# PCB-CMB-1.net
KiCad netlist of a schematic drawn in EAGLE
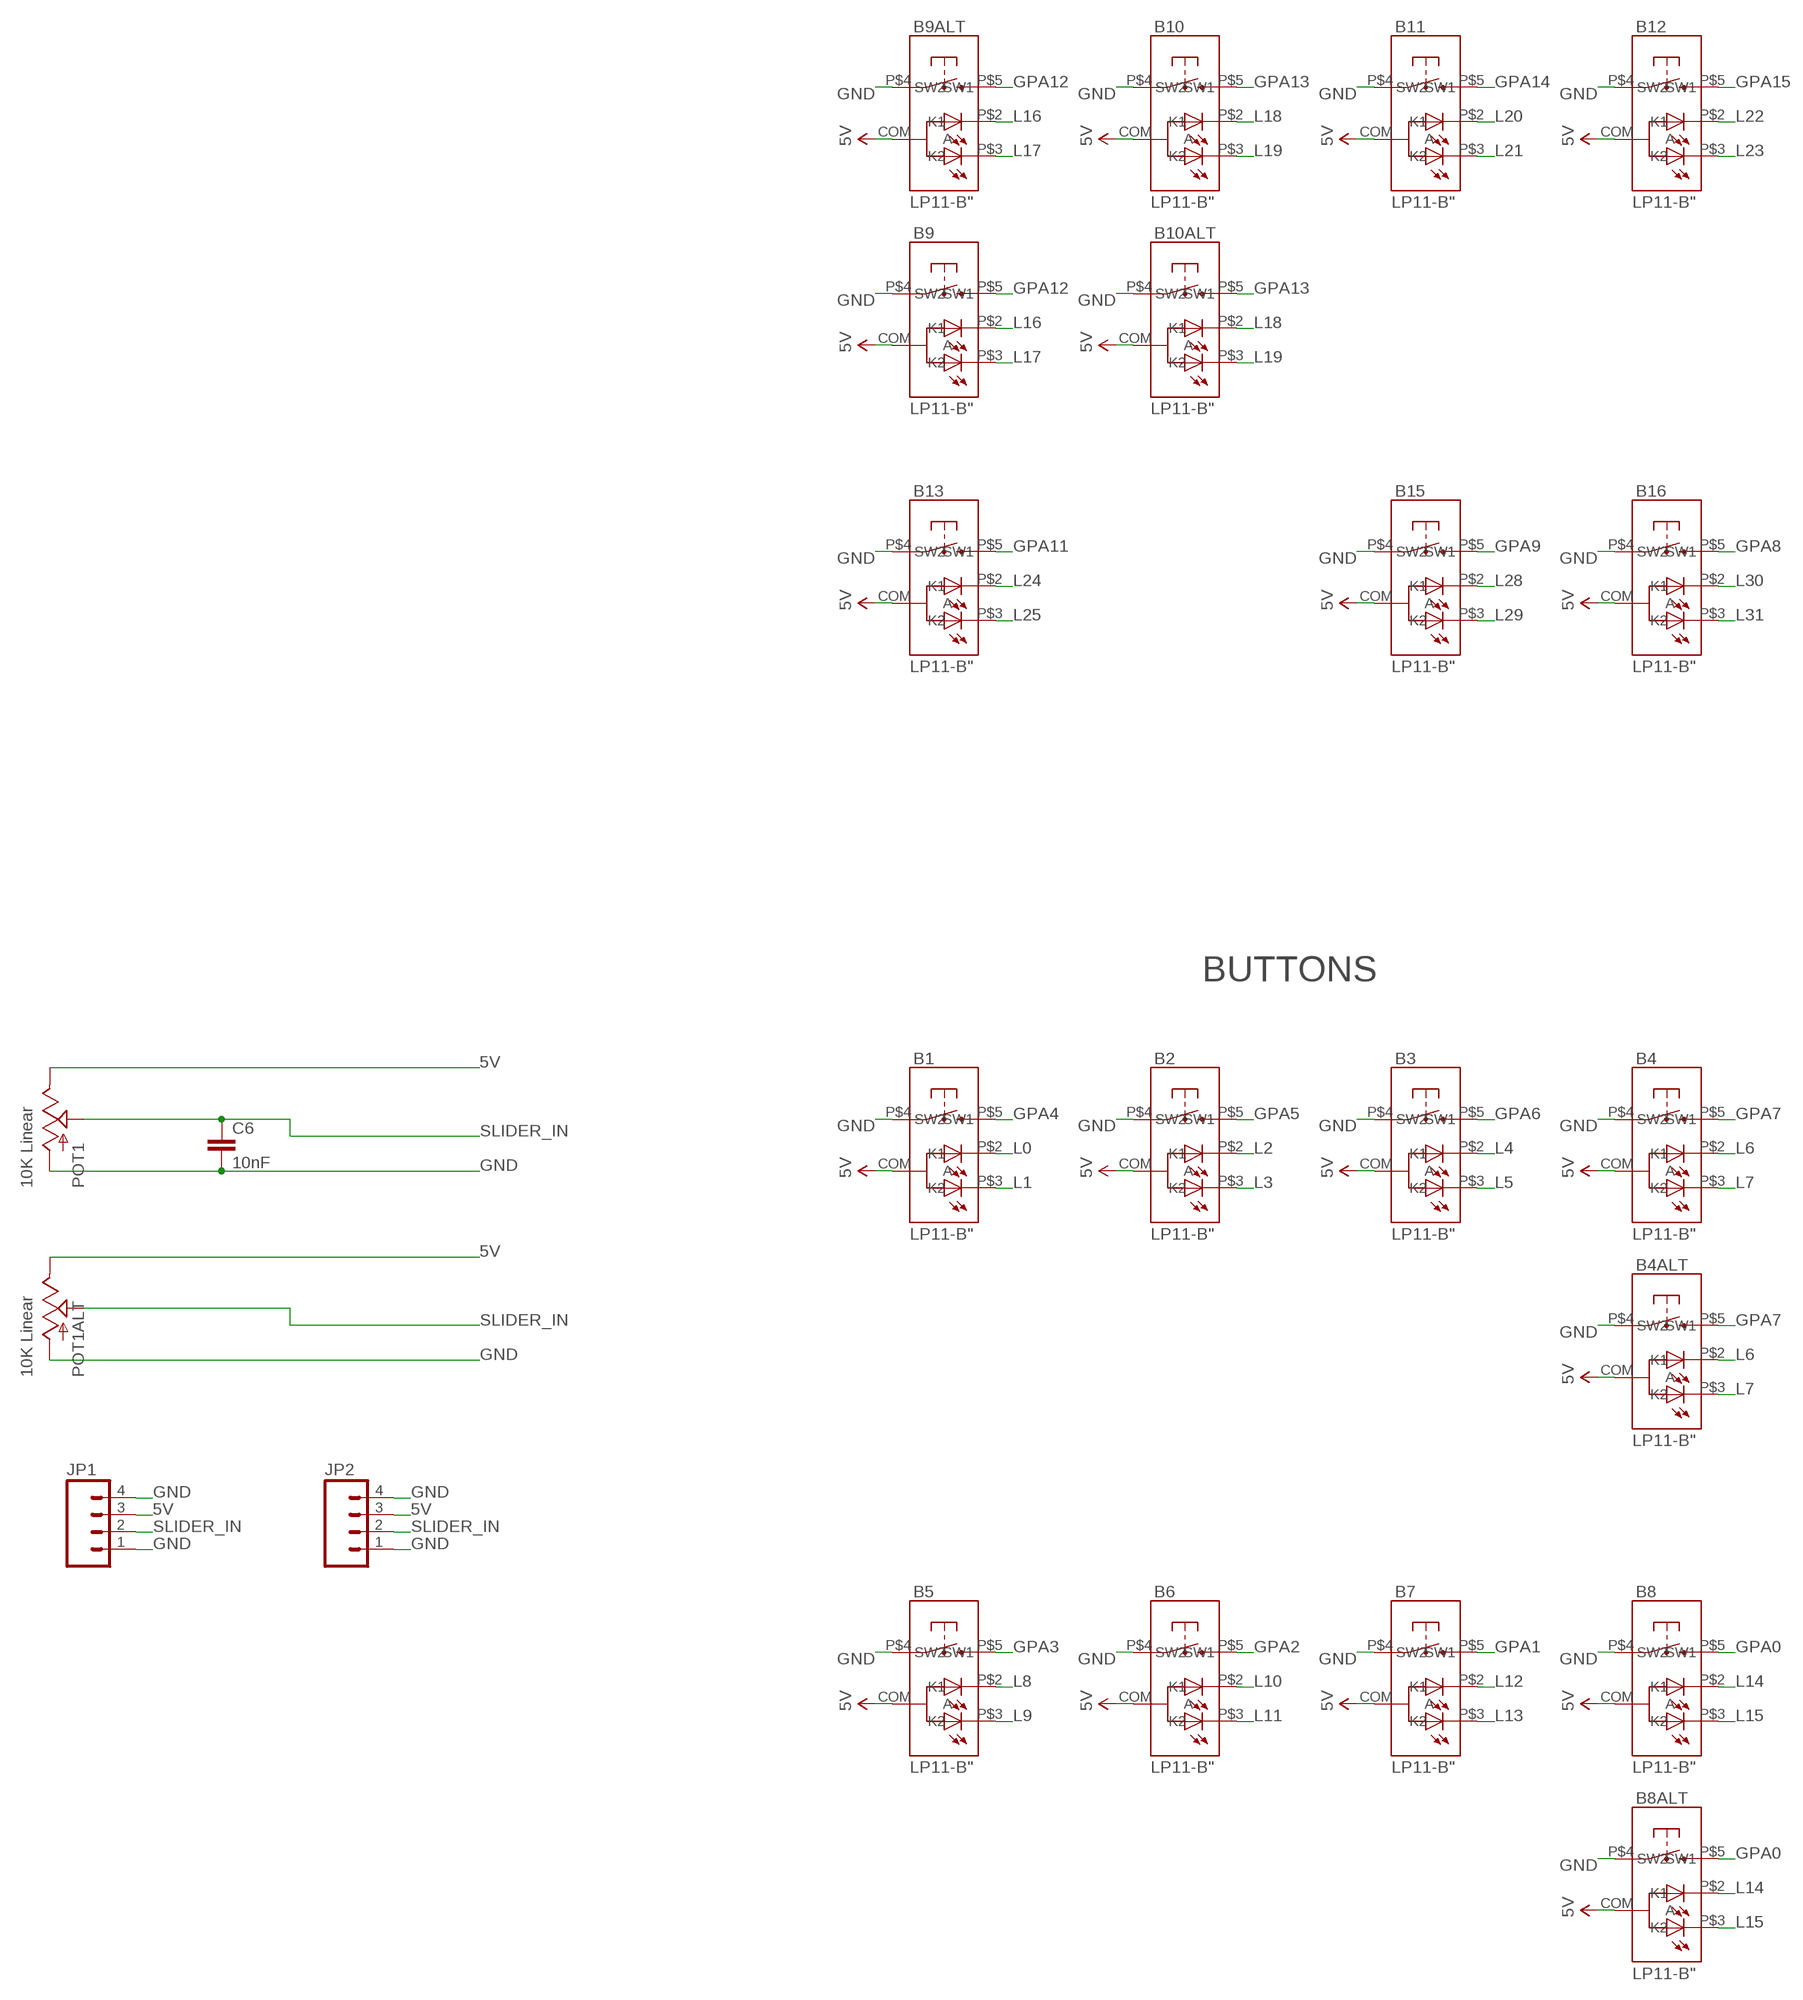
[diagram p0: schematic, sheet 1, part 1 of 2]
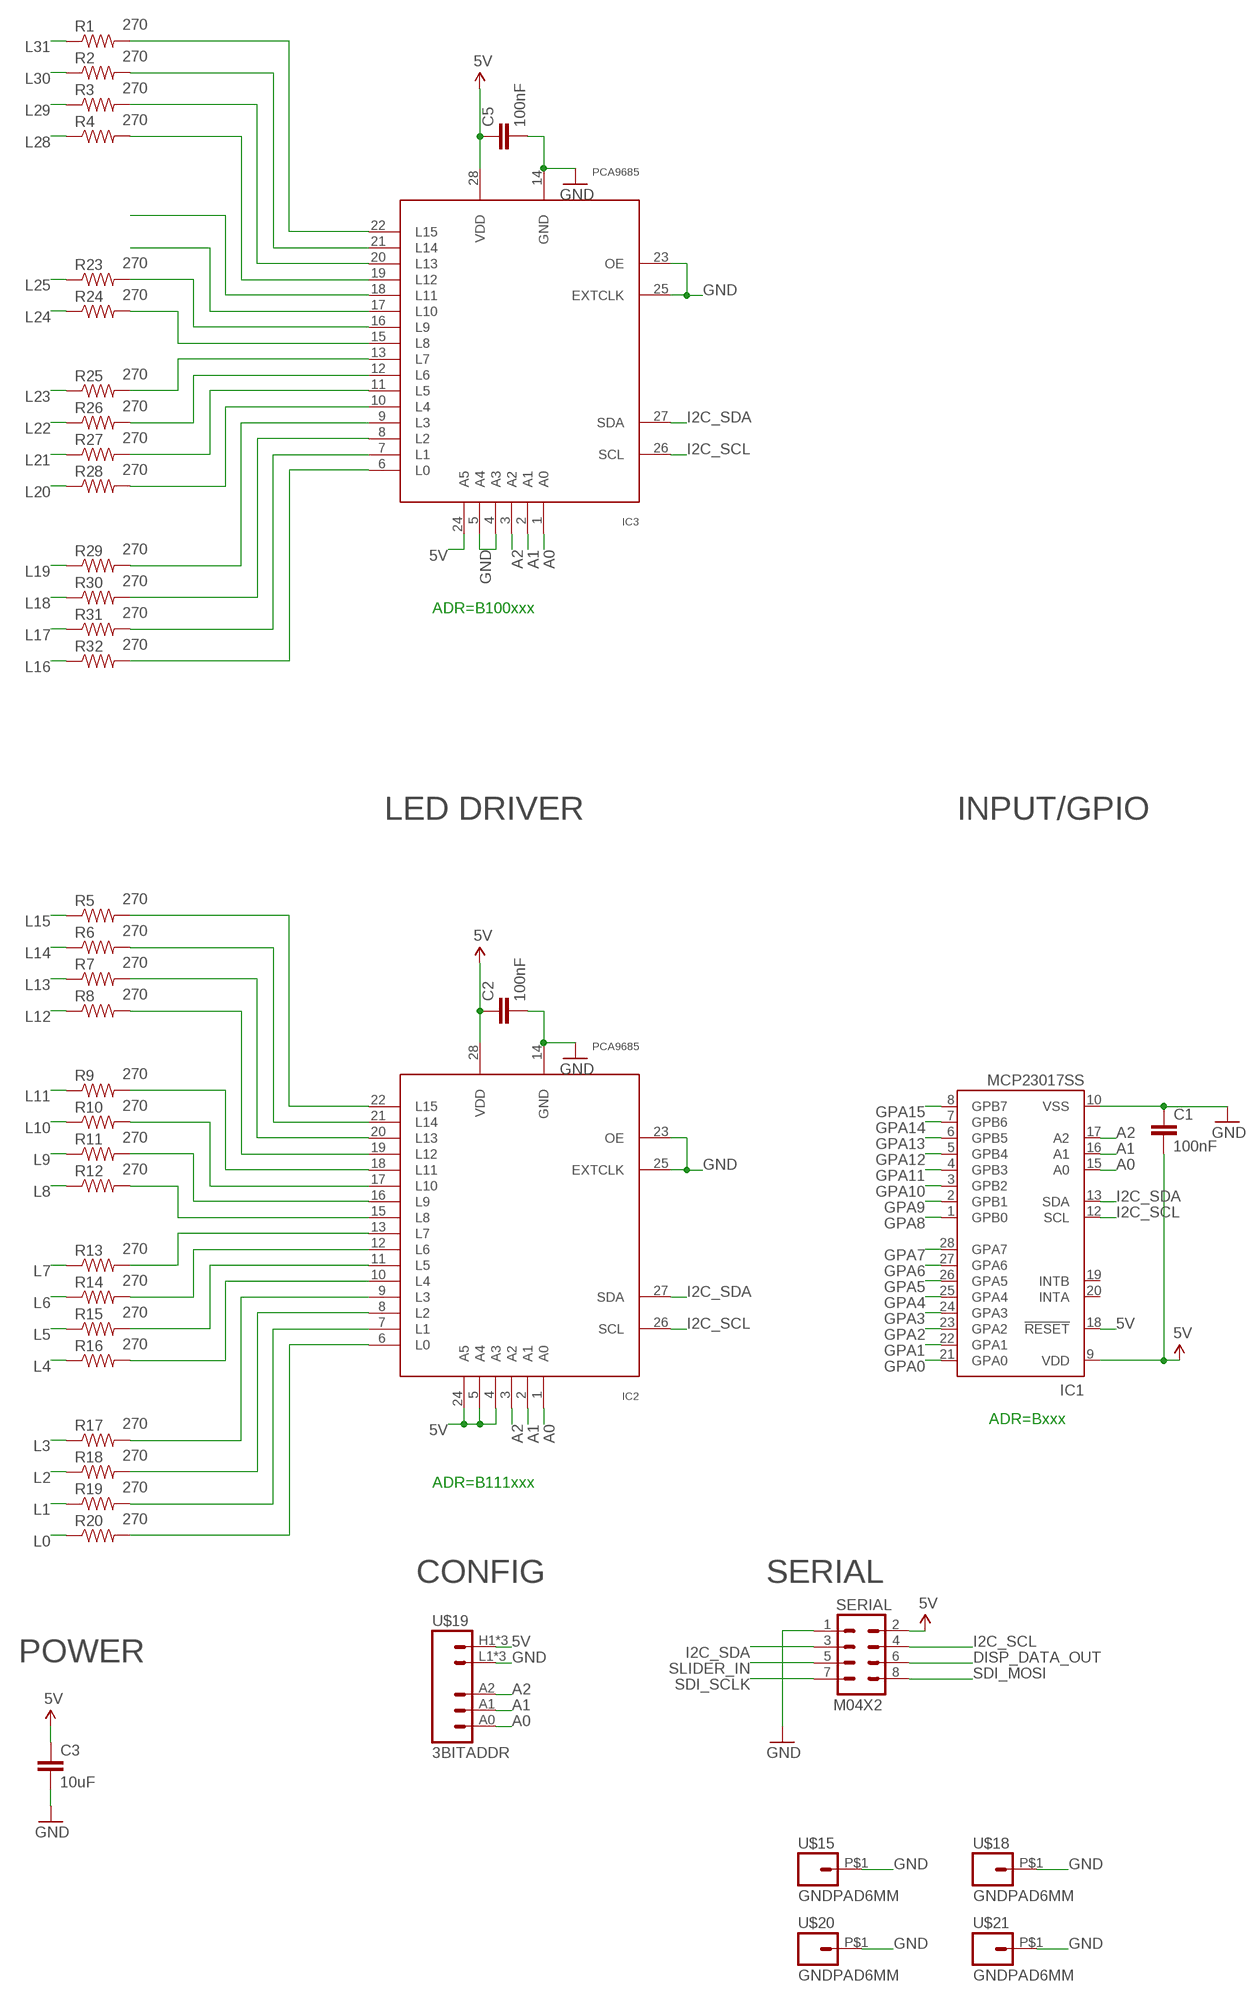
[diagram p1: schematic, sheet 1, part 2 of 2]

(export (version "E")
  (design (tool "Eeschema 10.0.6"))
  (components
    (comp (ref "B1")
      (value "LP11-B\"")
      (footprint "eagle-import:LP11")
      (libsource (lib "eagle-import") (part "LP11-B{dblquote}"))
    )
    (comp (ref "B2")
      (value "LP11-B\"")
      (footprint "eagle-import:LP11")
      (libsource (lib "eagle-import") (part "LP11-B{dblquote}"))
    )
    (comp (ref "B3")
      (value "LP11-B\"")
      (footprint "eagle-import:LP11")
      (libsource (lib "eagle-import") (part "LP11-B{dblquote}"))
    )
    (comp (ref "B4")
      (value "LP11-B\"")
      (footprint "eagle-import:LP11")
      (libsource (lib "eagle-import") (part "LP11-B{dblquote}"))
    )
    (comp (ref "B4ALT")
      (value "LP11-B\"")
      (footprint "eagle-import:LP11")
      (libsource (lib "eagle-import") (part "LP11-B{dblquote}"))
    )
    (comp (ref "B5")
      (value "LP11-B\"")
      (footprint "eagle-import:LP11")
      (libsource (lib "eagle-import") (part "LP11-B{dblquote}"))
    )
    (comp (ref "B6")
      (value "LP11-B\"")
      (footprint "eagle-import:LP11")
      (libsource (lib "eagle-import") (part "LP11-B{dblquote}"))
    )
    (comp (ref "B7")
      (value "LP11-B\"")
      (footprint "eagle-import:LP11")
      (libsource (lib "eagle-import") (part "LP11-B{dblquote}"))
    )
    (comp (ref "B8")
      (value "LP11-B\"")
      (footprint "eagle-import:LP11")
      (libsource (lib "eagle-import") (part "LP11-B{dblquote}"))
    )
    (comp (ref "B8ALT")
      (value "LP11-B\"")
      (footprint "eagle-import:LP11")
      (libsource (lib "eagle-import") (part "LP11-B{dblquote}"))
    )
    (comp (ref "B9")
      (value "LP11-B\"")
      (footprint "eagle-import:LP11")
      (libsource (lib "eagle-import") (part "LP11-B{dblquote}"))
    )
    (comp (ref "B9ALT")
      (value "LP11-B\"")
      (footprint "eagle-import:LP11")
      (libsource (lib "eagle-import") (part "LP11-B{dblquote}"))
    )
    (comp (ref "B10")
      (value "LP11-B\"")
      (footprint "eagle-import:LP11")
      (libsource (lib "eagle-import") (part "LP11-B{dblquote}"))
    )
    (comp (ref "B10ALT")
      (value "LP11-B\"")
      (footprint "eagle-import:LP11")
      (libsource (lib "eagle-import") (part "LP11-B{dblquote}"))
    )
    (comp (ref "B11")
      (value "LP11-B\"")
      (footprint "eagle-import:LP11")
      (libsource (lib "eagle-import") (part "LP11-B{dblquote}"))
    )
    (comp (ref "B12")
      (value "LP11-B\"")
      (footprint "eagle-import:LP11")
      (libsource (lib "eagle-import") (part "LP11-B{dblquote}"))
    )
    (comp (ref "B13")
      (value "LP11-B\"")
      (footprint "eagle-import:LP11")
      (libsource (lib "eagle-import") (part "LP11-B{dblquote}"))
    )
    (comp (ref "B15")
      (value "LP11-B\"")
      (footprint "eagle-import:LP11")
      (libsource (lib "eagle-import") (part "LP11-B{dblquote}"))
    )
    (comp (ref "B16")
      (value "LP11-B\"")
      (footprint "eagle-import:LP11")
      (libsource (lib "eagle-import") (part "LP11-B{dblquote}"))
    )
    (comp (ref "C1")
      (value "100nF")
      (footprint "eagle-import:0603-CAP")
      (libsource (lib "eagle-import") (part "CAP0603-CAP"))
    )
    (comp (ref "C2")
      (value "100nF")
      (footprint "eagle-import:0603-CAP")
      (libsource (lib "eagle-import") (part "CAP0603-CAP"))
    )
    (comp (ref "C3")
      (value "10uF")
      (footprint "eagle-import:0805")
      (libsource (lib "eagle-import") (part "CAP0805"))
    )
    (comp (ref "C5")
      (value "100nF")
      (footprint "eagle-import:0603-CAP")
      (libsource (lib "eagle-import") (part "CAP0603-CAP"))
    )
    (comp (ref "C6")
      (value "10nF")
      (footprint "eagle-import:0603-CAP")
      (libsource (lib "eagle-import") (part "CAP0603-CAP"))
    )
    (comp (ref "IC1")
      (value "MCP23017SS")
      (footprint "eagle-import:SSOP28")
      (fields
        (field (name "MF") "MICROCHIP")
        (field (name "MPN") "MCP23017-E/SS")
        (field (name "MPN_1") "MCP23017-E/SS")
        (field (name "OC_FARNELL") "1467674")
        (field (name "OC_NEWARK") "31K2960")
      )
      (libsource (lib "eagle-import") (part "MCP23017SS"))
    )
    (comp (ref "IC2")
      (value "PCA9685")
      (footprint "eagle-import:TSSOP28")
      (libsource (lib "eagle-import") (part "PCA9685"))
    )
    (comp (ref "IC3")
      (value "PCA9685")
      (footprint "eagle-import:TSSOP28")
      (libsource (lib "eagle-import") (part "PCA9685"))
    )
    (comp (ref "JP1")
      (value "M04PTH")
      (footprint "eagle-import:1X04")
      (libsource (lib "eagle-import") (part "M04PTH"))
    )
    (comp (ref "JP2")
      (value "M04PTH")
      (footprint "eagle-import:1X04")
      (libsource (lib "eagle-import") (part "M04PTH"))
    )
    (comp (ref "POT1")
      (value "10K Linear")
      (footprint "eagle-import:SLIDER20")
      (libsource (lib "eagle-import") (part "SLIDER20"))
    )
    (comp (ref "POT1ALT")
      (value "10K Linear")
      (footprint "eagle-import:SLIDER20")
      (libsource (lib "eagle-import") (part "SLIDER20"))
    )
    (comp (ref "R1")
      (value "270")
      (footprint "eagle-import:0603-RES")
      (libsource (lib "eagle-import") (part "RESISTOR0603-RES"))
    )
    (comp (ref "R2")
      (value "270")
      (footprint "eagle-import:0603-RES")
      (libsource (lib "eagle-import") (part "RESISTOR0603-RES"))
    )
    (comp (ref "R3")
      (value "270")
      (footprint "eagle-import:0603-RES")
      (libsource (lib "eagle-import") (part "RESISTOR0603-RES"))
    )
    (comp (ref "R4")
      (value "270")
      (footprint "eagle-import:0603-RES")
      (libsource (lib "eagle-import") (part "RESISTOR0603-RES"))
    )
    (comp (ref "R5")
      (value "270")
      (footprint "eagle-import:0603-RES")
      (libsource (lib "eagle-import") (part "RESISTOR0603-RES"))
    )
    (comp (ref "R6")
      (value "270")
      (footprint "eagle-import:0603-RES")
      (libsource (lib "eagle-import") (part "RESISTOR0603-RES"))
    )
    (comp (ref "R7")
      (value "270")
      (footprint "eagle-import:0603-RES")
      (libsource (lib "eagle-import") (part "RESISTOR0603-RES"))
    )
    (comp (ref "R8")
      (value "270")
      (footprint "eagle-import:0603-RES")
      (libsource (lib "eagle-import") (part "RESISTOR0603-RES"))
    )
    (comp (ref "R9")
      (value "270")
      (footprint "eagle-import:0603-RES")
      (libsource (lib "eagle-import") (part "RESISTOR0603-RES"))
    )
    (comp (ref "R10")
      (value "270")
      (footprint "eagle-import:0603-RES")
      (libsource (lib "eagle-import") (part "RESISTOR0603-RES"))
    )
    (comp (ref "R11")
      (value "270")
      (footprint "eagle-import:0603-RES")
      (libsource (lib "eagle-import") (part "RESISTOR0603-RES"))
    )
    (comp (ref "R12")
      (value "270")
      (footprint "eagle-import:0603-RES")
      (libsource (lib "eagle-import") (part "RESISTOR0603-RES"))
    )
    (comp (ref "R13")
      (value "270")
      (footprint "eagle-import:0603-RES")
      (libsource (lib "eagle-import") (part "RESISTOR0603-RES"))
    )
    (comp (ref "R14")
      (value "270")
      (footprint "eagle-import:0603-RES")
      (libsource (lib "eagle-import") (part "RESISTOR0603-RES"))
    )
    (comp (ref "R15")
      (value "270")
      (footprint "eagle-import:0603-RES")
      (libsource (lib "eagle-import") (part "RESISTOR0603-RES"))
    )
    (comp (ref "R16")
      (value "270")
      (footprint "eagle-import:0603-RES")
      (libsource (lib "eagle-import") (part "RESISTOR0603-RES"))
    )
    (comp (ref "R17")
      (value "270")
      (footprint "eagle-import:0603-RES")
      (libsource (lib "eagle-import") (part "RESISTOR0603-RES"))
    )
    (comp (ref "R18")
      (value "270")
      (footprint "eagle-import:0603-RES")
      (libsource (lib "eagle-import") (part "RESISTOR0603-RES"))
    )
    (comp (ref "R19")
      (value "270")
      (footprint "eagle-import:0603-RES")
      (libsource (lib "eagle-import") (part "RESISTOR0603-RES"))
    )
    (comp (ref "R20")
      (value "270")
      (footprint "eagle-import:0603-RES")
      (libsource (lib "eagle-import") (part "RESISTOR0603-RES"))
    )
    (comp (ref "R23")
      (value "270")
      (footprint "eagle-import:0603-RES")
      (libsource (lib "eagle-import") (part "RESISTOR0603-RES"))
    )
    (comp (ref "R24")
      (value "270")
      (footprint "eagle-import:0603-RES")
      (libsource (lib "eagle-import") (part "RESISTOR0603-RES"))
    )
    (comp (ref "R25")
      (value "270")
      (footprint "eagle-import:0603-RES")
      (libsource (lib "eagle-import") (part "RESISTOR0603-RES"))
    )
    (comp (ref "R26")
      (value "270")
      (footprint "eagle-import:0603-RES")
      (libsource (lib "eagle-import") (part "RESISTOR0603-RES"))
    )
    (comp (ref "R27")
      (value "270")
      (footprint "eagle-import:0603-RES")
      (libsource (lib "eagle-import") (part "RESISTOR0603-RES"))
    )
    (comp (ref "R28")
      (value "270")
      (footprint "eagle-import:0603-RES")
      (libsource (lib "eagle-import") (part "RESISTOR0603-RES"))
    )
    (comp (ref "R29")
      (value "270")
      (footprint "eagle-import:0603-RES")
      (libsource (lib "eagle-import") (part "RESISTOR0603-RES"))
    )
    (comp (ref "R30")
      (value "270")
      (footprint "eagle-import:0603-RES")
      (libsource (lib "eagle-import") (part "RESISTOR0603-RES"))
    )
    (comp (ref "R31")
      (value "270")
      (footprint "eagle-import:0603-RES")
      (libsource (lib "eagle-import") (part "RESISTOR0603-RES"))
    )
    (comp (ref "R32")
      (value "270")
      (footprint "eagle-import:0603-RES")
      (libsource (lib "eagle-import") (part "RESISTOR0603-RES"))
    )
    (comp (ref "SERIAL")
      (value "M04X2")
      (footprint "eagle-import:2X4")
      (libsource (lib "eagle-import") (part "M04X2"))
    )
    (comp (ref "U$15")
      (value "GNDPAD6MM")
      (footprint "eagle-import:3.2MMPAD6MM")
      (libsource (lib "eagle-import") (part "GNDPAD6MM"))
    )
    (comp (ref "U$18")
      (value "GNDPAD6MM")
      (footprint "eagle-import:3.2MMPAD6MM")
      (libsource (lib "eagle-import") (part "GNDPAD6MM"))
    )
    (comp (ref "U$19")
      (value "3BITADDR")
      (footprint "eagle-import:3BITADDR")
      (libsource (lib "eagle-import") (part "3BITADDR"))
    )
    (comp (ref "U$20")
      (value "GNDPAD6MM")
      (footprint "eagle-import:3.2MMPAD6MM")
      (libsource (lib "eagle-import") (part "GNDPAD6MM"))
    )
    (comp (ref "U$21")
      (value "GNDPAD6MM")
      (footprint "eagle-import:3.2MMPAD6MM")
      (libsource (lib "eagle-import") (part "GNDPAD6MM"))
    )
  )
  (nets
    (net (code "1") (name "5V") (class "Default")
      (node (ref "B1") (pin "COM") (pinfunction "A_COM") (pintype "bidirectional"))
      (node (ref "B10") (pin "COM") (pinfunction "A_COM") (pintype "bidirectional"))
      (node (ref "B10ALT") (pin "COM") (pinfunction "A_COM") (pintype "bidirectional"))
      (node (ref "B11") (pin "COM") (pinfunction "A_COM") (pintype "bidirectional"))
      (node (ref "B12") (pin "COM") (pinfunction "A_COM") (pintype "bidirectional"))
      (node (ref "B13") (pin "COM") (pinfunction "A_COM") (pintype "bidirectional"))
      (node (ref "B15") (pin "COM") (pinfunction "A_COM") (pintype "bidirectional"))
      (node (ref "B16") (pin "COM") (pinfunction "A_COM") (pintype "bidirectional"))
      (node (ref "B2") (pin "COM") (pinfunction "A_COM") (pintype "bidirectional"))
      (node (ref "B3") (pin "COM") (pinfunction "A_COM") (pintype "bidirectional"))
      (node (ref "B4") (pin "COM") (pinfunction "A_COM") (pintype "bidirectional"))
      (node (ref "B4ALT") (pin "COM") (pinfunction "A_COM") (pintype "bidirectional"))
      (node (ref "B5") (pin "COM") (pinfunction "A_COM") (pintype "bidirectional"))
      (node (ref "B6") (pin "COM") (pinfunction "A_COM") (pintype "bidirectional"))
      (node (ref "B7") (pin "COM") (pinfunction "A_COM") (pintype "bidirectional"))
      (node (ref "B8") (pin "COM") (pinfunction "A_COM") (pintype "bidirectional"))
      (node (ref "B8ALT") (pin "COM") (pinfunction "A_COM") (pintype "bidirectional"))
      (node (ref "B9") (pin "COM") (pinfunction "A_COM") (pintype "bidirectional"))
      (node (ref "B9ALT") (pin "COM") (pinfunction "A_COM") (pintype "bidirectional"))
      (node (ref "C1") (pin "2") (pinfunction "2_2") (pintype "passive"))
      (node (ref "C2") (pin "1") (pinfunction "1_1") (pintype "passive"))
      (node (ref "C3") (pin "1") (pinfunction "1_1") (pintype "passive"))
      (node (ref "C5") (pin "1") (pinfunction "1_1") (pintype "passive"))
      (node (ref "IC1") (pin "18") (pinfunction "~{RESET}_18") (pintype "input"))
      (node (ref "IC1") (pin "9") (pinfunction "VDD_9") (pintype "power_in"))
      (node (ref "IC2") (pin "24") (pinfunction "A5_24") (pintype "input"))
      (node (ref "IC2") (pin "28") (pinfunction "VDD_28") (pintype "power_in"))
      (node (ref "IC2") (pin "4") (pinfunction "A3_4") (pintype "input"))
      (node (ref "IC2") (pin "5") (pinfunction "A4_5") (pintype "input"))
      (node (ref "IC3") (pin "24") (pinfunction "A5_24") (pintype "input"))
      (node (ref "IC3") (pin "28") (pinfunction "VDD_28") (pintype "power_in"))
      (node (ref "JP1") (pin "3") (pinfunction "3_3") (pintype "passive"))
      (node (ref "JP2") (pin "3") (pinfunction "3_3") (pintype "passive"))
      (node (ref "POT1") (pin "1") (pinfunction "E_1") (pintype "passive"))
      (node (ref "POT1ALT") (pin "1") (pinfunction "E_1") (pintype "passive"))
      (node (ref "SERIAL") (pin "2") (pinfunction "2_2") (pintype "passive"))
      (node (ref "U$19") (pin "H1") (pinfunction "VCC_H1") (pintype "passive"))
      (node (ref "U$19") (pin "H2") (pinfunction "VCC_H2") (pintype "passive"))
      (node (ref "U$19") (pin "H3") (pinfunction "VCC_H3") (pintype "passive"))
    )
    (net (code "2") (name "A0") (class "Default")
      (node (ref "IC1") (pin "15") (pinfunction "A0_15") (pintype "input"))
      (node (ref "IC2") (pin "1") (pinfunction "A0_1") (pintype "input"))
      (node (ref "IC3") (pin "1") (pinfunction "A0_1") (pintype "input"))
      (node (ref "U$19") (pin "A0") (pinfunction "A0_A0") (pintype "passive"))
    )
    (net (code "3") (name "A1") (class "Default")
      (node (ref "IC1") (pin "16") (pinfunction "A1_16") (pintype "input"))
      (node (ref "IC2") (pin "2") (pinfunction "A1_2") (pintype "input"))
      (node (ref "IC3") (pin "2") (pinfunction "A1_2") (pintype "input"))
      (node (ref "U$19") (pin "A1") (pinfunction "A1_A1") (pintype "passive"))
    )
    (net (code "4") (name "A2") (class "Default")
      (node (ref "IC1") (pin "17") (pinfunction "A2_17") (pintype "input"))
      (node (ref "IC2") (pin "3") (pinfunction "A2_3") (pintype "input"))
      (node (ref "IC3") (pin "3") (pinfunction "A2_3") (pintype "input"))
      (node (ref "U$19") (pin "A2") (pinfunction "A2_A2") (pintype "passive"))
    )
    (net (code "5") (name "DISP_DATA_OUT") (class "Default")
      (node (ref "SERIAL") (pin "6") (pinfunction "6_6") (pintype "passive"))
    )
    (net (code "6") (name "GND") (class "Default")
      (node (ref "B1") (pin "P$4") (pinfunction "SW1_P$4") (pintype "bidirectional"))
      (node (ref "B10") (pin "P$4") (pinfunction "SW1_P$4") (pintype "bidirectional"))
      (node (ref "B10ALT") (pin "P$4") (pinfunction "SW1_P$4") (pintype "bidirectional"))
      (node (ref "B11") (pin "P$4") (pinfunction "SW1_P$4") (pintype "bidirectional"))
      (node (ref "B12") (pin "P$4") (pinfunction "SW1_P$4") (pintype "bidirectional"))
      (node (ref "B13") (pin "P$4") (pinfunction "SW1_P$4") (pintype "bidirectional"))
      (node (ref "B15") (pin "P$4") (pinfunction "SW1_P$4") (pintype "bidirectional"))
      (node (ref "B16") (pin "P$4") (pinfunction "SW1_P$4") (pintype "bidirectional"))
      (node (ref "B2") (pin "P$4") (pinfunction "SW1_P$4") (pintype "bidirectional"))
      (node (ref "B3") (pin "P$4") (pinfunction "SW1_P$4") (pintype "bidirectional"))
      (node (ref "B4") (pin "P$4") (pinfunction "SW1_P$4") (pintype "bidirectional"))
      (node (ref "B4ALT") (pin "P$4") (pinfunction "SW1_P$4") (pintype "bidirectional"))
      (node (ref "B5") (pin "P$4") (pinfunction "SW1_P$4") (pintype "bidirectional"))
      (node (ref "B6") (pin "P$4") (pinfunction "SW1_P$4") (pintype "bidirectional"))
      (node (ref "B7") (pin "P$4") (pinfunction "SW1_P$4") (pintype "bidirectional"))
      (node (ref "B8") (pin "P$4") (pinfunction "SW1_P$4") (pintype "bidirectional"))
      (node (ref "B8ALT") (pin "P$4") (pinfunction "SW1_P$4") (pintype "bidirectional"))
      (node (ref "B9") (pin "P$4") (pinfunction "SW1_P$4") (pintype "bidirectional"))
      (node (ref "B9ALT") (pin "P$4") (pinfunction "SW1_P$4") (pintype "bidirectional"))
      (node (ref "C1") (pin "1") (pinfunction "1_1") (pintype "passive"))
      (node (ref "C2") (pin "2") (pinfunction "2_2") (pintype "passive"))
      (node (ref "C3") (pin "2") (pinfunction "2_2") (pintype "passive"))
      (node (ref "C5") (pin "2") (pinfunction "2_2") (pintype "passive"))
      (node (ref "C6") (pin "2") (pinfunction "2_2") (pintype "passive"))
      (node (ref "IC1") (pin "10") (pinfunction "VSS_10") (pintype "power_in"))
      (node (ref "IC2") (pin "14") (pinfunction "GND_14") (pintype "power_in"))
      (node (ref "IC2") (pin "23") (pinfunction "OE_23") (pintype "input"))
      (node (ref "IC2") (pin "25") (pinfunction "EXTCLK_25") (pintype "input"))
      (node (ref "IC3") (pin "14") (pinfunction "GND_14") (pintype "power_in"))
      (node (ref "IC3") (pin "23") (pinfunction "OE_23") (pintype "input"))
      (node (ref "IC3") (pin "25") (pinfunction "EXTCLK_25") (pintype "input"))
      (node (ref "IC3") (pin "4") (pinfunction "A3_4") (pintype "input"))
      (node (ref "IC3") (pin "5") (pinfunction "A4_5") (pintype "input"))
      (node (ref "JP1") (pin "1") (pinfunction "1_1") (pintype "passive"))
      (node (ref "JP1") (pin "4") (pinfunction "4_4") (pintype "passive"))
      (node (ref "JP2") (pin "1") (pinfunction "1_1") (pintype "passive"))
      (node (ref "JP2") (pin "4") (pinfunction "4_4") (pintype "passive"))
      (node (ref "POT1") (pin "3") (pinfunction "A_3") (pintype "passive"))
      (node (ref "POT1ALT") (pin "3") (pinfunction "A_3") (pintype "passive"))
      (node (ref "SERIAL") (pin "1") (pinfunction "1_1") (pintype "passive"))
      (node (ref "U$15") (pin "P$1") (pinfunction "1_P$1") (pintype "passive"))
      (node (ref "U$18") (pin "P$1") (pinfunction "1_P$1") (pintype "passive"))
      (node (ref "U$19") (pin "L1") (pinfunction "GND_L1") (pintype "passive"))
      (node (ref "U$19") (pin "L2") (pinfunction "GND_L2") (pintype "passive"))
      (node (ref "U$19") (pin "L3") (pinfunction "GND_L3") (pintype "passive"))
      (node (ref "U$20") (pin "P$1") (pinfunction "1_P$1") (pintype "passive"))
      (node (ref "U$21") (pin "P$1") (pinfunction "1_P$1") (pintype "passive"))
    )
    (net (code "7") (name "GPA0") (class "Default")
      (node (ref "B8") (pin "P$5") (pinfunction "SW2_P$5") (pintype "bidirectional"))
      (node (ref "B8ALT") (pin "P$5") (pinfunction "SW2_P$5") (pintype "bidirectional"))
      (node (ref "IC1") (pin "21") (pinfunction "GPA0_21") (pintype "bidirectional"))
    )
    (net (code "8") (name "GPA1") (class "Default")
      (node (ref "B7") (pin "P$5") (pinfunction "SW2_P$5") (pintype "bidirectional"))
      (node (ref "IC1") (pin "22") (pinfunction "GPA1_22") (pintype "bidirectional"))
    )
    (net (code "9") (name "GPA2") (class "Default")
      (node (ref "B6") (pin "P$5") (pinfunction "SW2_P$5") (pintype "bidirectional"))
      (node (ref "IC1") (pin "23") (pinfunction "GPA2_23") (pintype "bidirectional"))
    )
    (net (code "10") (name "GPA3") (class "Default")
      (node (ref "B5") (pin "P$5") (pinfunction "SW2_P$5") (pintype "bidirectional"))
      (node (ref "IC1") (pin "24") (pinfunction "GPA3_24") (pintype "bidirectional"))
    )
    (net (code "11") (name "GPA4") (class "Default")
      (node (ref "B1") (pin "P$5") (pinfunction "SW2_P$5") (pintype "bidirectional"))
      (node (ref "IC1") (pin "25") (pinfunction "GPA4_25") (pintype "bidirectional"))
    )
    (net (code "12") (name "GPA5") (class "Default")
      (node (ref "B2") (pin "P$5") (pinfunction "SW2_P$5") (pintype "bidirectional"))
      (node (ref "IC1") (pin "26") (pinfunction "GPA5_26") (pintype "bidirectional"))
    )
    (net (code "13") (name "GPA6") (class "Default")
      (node (ref "B3") (pin "P$5") (pinfunction "SW2_P$5") (pintype "bidirectional"))
      (node (ref "IC1") (pin "27") (pinfunction "GPA6_27") (pintype "bidirectional"))
    )
    (net (code "14") (name "GPA7") (class "Default")
      (node (ref "B4") (pin "P$5") (pinfunction "SW2_P$5") (pintype "bidirectional"))
      (node (ref "B4ALT") (pin "P$5") (pinfunction "SW2_P$5") (pintype "bidirectional"))
      (node (ref "IC1") (pin "28") (pinfunction "GPA7_28") (pintype "bidirectional"))
    )
    (net (code "15") (name "GPA8") (class "Default")
      (node (ref "B16") (pin "P$5") (pinfunction "SW2_P$5") (pintype "bidirectional"))
      (node (ref "IC1") (pin "1") (pinfunction "GPB0_1") (pintype "bidirectional"))
    )
    (net (code "16") (name "GPA9") (class "Default")
      (node (ref "B15") (pin "P$5") (pinfunction "SW2_P$5") (pintype "bidirectional"))
      (node (ref "IC1") (pin "2") (pinfunction "GPB1_2") (pintype "bidirectional"))
    )
    (net (code "17") (name "GPA10") (class "Default")
      (node (ref "IC1") (pin "3") (pinfunction "GPB2_3") (pintype "bidirectional"))
    )
    (net (code "18") (name "GPA11") (class "Default")
      (node (ref "B13") (pin "P$5") (pinfunction "SW2_P$5") (pintype "bidirectional"))
      (node (ref "IC1") (pin "4") (pinfunction "GPB3_4") (pintype "bidirectional"))
    )
    (net (code "19") (name "GPA12") (class "Default")
      (node (ref "B9") (pin "P$5") (pinfunction "SW2_P$5") (pintype "bidirectional"))
      (node (ref "B9ALT") (pin "P$5") (pinfunction "SW2_P$5") (pintype "bidirectional"))
      (node (ref "IC1") (pin "5") (pinfunction "GPB4_5") (pintype "bidirectional"))
    )
    (net (code "20") (name "GPA13") (class "Default")
      (node (ref "B10") (pin "P$5") (pinfunction "SW2_P$5") (pintype "bidirectional"))
      (node (ref "B10ALT") (pin "P$5") (pinfunction "SW2_P$5") (pintype "bidirectional"))
      (node (ref "IC1") (pin "6") (pinfunction "GPB5_6") (pintype "bidirectional"))
    )
    (net (code "21") (name "GPA14") (class "Default")
      (node (ref "B11") (pin "P$5") (pinfunction "SW2_P$5") (pintype "bidirectional"))
      (node (ref "IC1") (pin "7") (pinfunction "GPB6_7") (pintype "bidirectional"))
    )
    (net (code "22") (name "GPA15") (class "Default")
      (node (ref "B12") (pin "P$5") (pinfunction "SW2_P$5") (pintype "bidirectional"))
      (node (ref "IC1") (pin "8") (pinfunction "GPB7_8") (pintype "bidirectional"))
    )
    (net (code "23") (name "I2C_SCL") (class "Default")
      (node (ref "IC1") (pin "12") (pinfunction "SCL_12") (pintype "input"))
      (node (ref "IC2") (pin "26") (pinfunction "SCL_26") (pintype "input"))
      (node (ref "IC3") (pin "26") (pinfunction "SCL_26") (pintype "input"))
      (node (ref "SERIAL") (pin "4") (pinfunction "4_4") (pintype "passive"))
    )
    (net (code "24") (name "I2C_SDA") (class "Default")
      (node (ref "IC1") (pin "13") (pinfunction "SDA_13") (pintype "bidirectional"))
      (node (ref "IC2") (pin "27") (pinfunction "SDA_27") (pintype "input"))
      (node (ref "IC3") (pin "27") (pinfunction "SDA_27") (pintype "input"))
      (node (ref "SERIAL") (pin "3") (pinfunction "3_3") (pintype "passive"))
    )
    (net (code "25") (name "L0") (class "Default")
      (node (ref "B1") (pin "P$2") (pinfunction "K1_P$2") (pintype "bidirectional"))
      (node (ref "R20") (pin "1") (pinfunction "1_1") (pintype "passive"))
    )
    (net (code "26") (name "L1") (class "Default")
      (node (ref "B1") (pin "P$3") (pinfunction "K2_P$3") (pintype "bidirectional"))
      (node (ref "R19") (pin "1") (pinfunction "1_1") (pintype "passive"))
    )
    (net (code "27") (name "L2") (class "Default")
      (node (ref "B2") (pin "P$2") (pinfunction "K1_P$2") (pintype "bidirectional"))
      (node (ref "R18") (pin "1") (pinfunction "1_1") (pintype "passive"))
    )
    (net (code "28") (name "L3") (class "Default")
      (node (ref "B2") (pin "P$3") (pinfunction "K2_P$3") (pintype "bidirectional"))
      (node (ref "R17") (pin "1") (pinfunction "1_1") (pintype "passive"))
    )
    (net (code "29") (name "L4") (class "Default")
      (node (ref "B3") (pin "P$2") (pinfunction "K1_P$2") (pintype "bidirectional"))
      (node (ref "R16") (pin "1") (pinfunction "1_1") (pintype "passive"))
    )
    (net (code "30") (name "L5") (class "Default")
      (node (ref "B3") (pin "P$3") (pinfunction "K2_P$3") (pintype "bidirectional"))
      (node (ref "R15") (pin "1") (pinfunction "1_1") (pintype "passive"))
    )
    (net (code "31") (name "L6") (class "Default")
      (node (ref "B4") (pin "P$2") (pinfunction "K1_P$2") (pintype "bidirectional"))
      (node (ref "B4ALT") (pin "P$2") (pinfunction "K1_P$2") (pintype "bidirectional"))
      (node (ref "R14") (pin "1") (pinfunction "1_1") (pintype "passive"))
    )
    (net (code "32") (name "L7") (class "Default")
      (node (ref "B4") (pin "P$3") (pinfunction "K2_P$3") (pintype "bidirectional"))
      (node (ref "B4ALT") (pin "P$3") (pinfunction "K2_P$3") (pintype "bidirectional"))
      (node (ref "R13") (pin "1") (pinfunction "1_1") (pintype "passive"))
    )
    (net (code "33") (name "L8") (class "Default")
      (node (ref "B5") (pin "P$2") (pinfunction "K1_P$2") (pintype "bidirectional"))
      (node (ref "R12") (pin "1") (pinfunction "1_1") (pintype "passive"))
    )
    (net (code "34") (name "L9") (class "Default")
      (node (ref "B5") (pin "P$3") (pinfunction "K2_P$3") (pintype "bidirectional"))
      (node (ref "R11") (pin "1") (pinfunction "1_1") (pintype "passive"))
    )
    (net (code "35") (name "L10") (class "Default")
      (node (ref "B6") (pin "P$2") (pinfunction "K1_P$2") (pintype "bidirectional"))
      (node (ref "R10") (pin "1") (pinfunction "1_1") (pintype "passive"))
    )
    (net (code "36") (name "L11") (class "Default")
      (node (ref "B6") (pin "P$3") (pinfunction "K2_P$3") (pintype "bidirectional"))
      (node (ref "R9") (pin "1") (pinfunction "1_1") (pintype "passive"))
    )
    (net (code "37") (name "L12") (class "Default")
      (node (ref "B7") (pin "P$2") (pinfunction "K1_P$2") (pintype "bidirectional"))
      (node (ref "R8") (pin "1") (pinfunction "1_1") (pintype "passive"))
    )
    (net (code "38") (name "L13") (class "Default")
      (node (ref "B7") (pin "P$3") (pinfunction "K2_P$3") (pintype "bidirectional"))
      (node (ref "R7") (pin "1") (pinfunction "1_1") (pintype "passive"))
    )
    (net (code "39") (name "L14") (class "Default")
      (node (ref "B8") (pin "P$2") (pinfunction "K1_P$2") (pintype "bidirectional"))
      (node (ref "B8ALT") (pin "P$2") (pinfunction "K1_P$2") (pintype "bidirectional"))
      (node (ref "R6") (pin "1") (pinfunction "1_1") (pintype "passive"))
    )
    (net (code "40") (name "L15") (class "Default")
      (node (ref "B8") (pin "P$3") (pinfunction "K2_P$3") (pintype "bidirectional"))
      (node (ref "B8ALT") (pin "P$3") (pinfunction "K2_P$3") (pintype "bidirectional"))
      (node (ref "R5") (pin "1") (pinfunction "1_1") (pintype "passive"))
    )
    (net (code "41") (name "L16") (class "Default")
      (node (ref "B9") (pin "P$2") (pinfunction "K1_P$2") (pintype "bidirectional"))
      (node (ref "B9ALT") (pin "P$2") (pinfunction "K1_P$2") (pintype "bidirectional"))
      (node (ref "R32") (pin "1") (pinfunction "1_1") (pintype "passive"))
    )
    (net (code "42") (name "L17") (class "Default")
      (node (ref "B9") (pin "P$3") (pinfunction "K2_P$3") (pintype "bidirectional"))
      (node (ref "B9ALT") (pin "P$3") (pinfunction "K2_P$3") (pintype "bidirectional"))
      (node (ref "R31") (pin "1") (pinfunction "1_1") (pintype "passive"))
    )
    (net (code "43") (name "L18") (class "Default")
      (node (ref "B10") (pin "P$2") (pinfunction "K1_P$2") (pintype "bidirectional"))
      (node (ref "B10ALT") (pin "P$2") (pinfunction "K1_P$2") (pintype "bidirectional"))
      (node (ref "R30") (pin "1") (pinfunction "1_1") (pintype "passive"))
    )
    (net (code "44") (name "L19") (class "Default")
      (node (ref "B10") (pin "P$3") (pinfunction "K2_P$3") (pintype "bidirectional"))
      (node (ref "B10ALT") (pin "P$3") (pinfunction "K2_P$3") (pintype "bidirectional"))
      (node (ref "R29") (pin "1") (pinfunction "1_1") (pintype "passive"))
    )
    (net (code "45") (name "L20") (class "Default")
      (node (ref "B11") (pin "P$2") (pinfunction "K1_P$2") (pintype "bidirectional"))
      (node (ref "R28") (pin "1") (pinfunction "1_1") (pintype "passive"))
    )
    (net (code "46") (name "L21") (class "Default")
      (node (ref "B11") (pin "P$3") (pinfunction "K2_P$3") (pintype "bidirectional"))
      (node (ref "R27") (pin "1") (pinfunction "1_1") (pintype "passive"))
    )
    (net (code "47") (name "L22") (class "Default")
      (node (ref "B12") (pin "P$2") (pinfunction "K1_P$2") (pintype "bidirectional"))
      (node (ref "R26") (pin "1") (pinfunction "1_1") (pintype "passive"))
    )
    (net (code "48") (name "L23") (class "Default")
      (node (ref "B12") (pin "P$3") (pinfunction "K2_P$3") (pintype "bidirectional"))
      (node (ref "R25") (pin "1") (pinfunction "1_1") (pintype "passive"))
    )
    (net (code "49") (name "L24") (class "Default")
      (node (ref "B13") (pin "P$2") (pinfunction "K1_P$2") (pintype "bidirectional"))
      (node (ref "R24") (pin "1") (pinfunction "1_1") (pintype "passive"))
    )
    (net (code "50") (name "L25") (class "Default")
      (node (ref "B13") (pin "P$3") (pinfunction "K2_P$3") (pintype "bidirectional"))
      (node (ref "R23") (pin "1") (pinfunction "1_1") (pintype "passive"))
    )
    (net (code "51") (name "L28") (class "Default")
      (node (ref "B15") (pin "P$2") (pinfunction "K1_P$2") (pintype "bidirectional"))
      (node (ref "R4") (pin "1") (pinfunction "1_1") (pintype "passive"))
    )
    (net (code "52") (name "L29") (class "Default")
      (node (ref "B15") (pin "P$3") (pinfunction "K2_P$3") (pintype "bidirectional"))
      (node (ref "R3") (pin "1") (pinfunction "1_1") (pintype "passive"))
    )
    (net (code "53") (name "L30") (class "Default")
      (node (ref "B16") (pin "P$2") (pinfunction "K1_P$2") (pintype "bidirectional"))
      (node (ref "R2") (pin "1") (pinfunction "1_1") (pintype "passive"))
    )
    (net (code "54") (name "L31") (class "Default")
      (node (ref "B16") (pin "P$3") (pinfunction "K2_P$3") (pintype "bidirectional"))
      (node (ref "R1") (pin "1") (pinfunction "1_1") (pintype "passive"))
    )
    (net (code "55") (name "Net-(IC2-L0)") (class "Default")
      (node (ref "IC2") (pin "6") (pinfunction "L0_6") (pintype "output"))
      (node (ref "R20") (pin "2") (pinfunction "2_2") (pintype "passive"))
    )
    (net (code "56") (name "Net-(IC2-L1)") (class "Default")
      (node (ref "IC2") (pin "7") (pinfunction "L1_7") (pintype "output"))
      (node (ref "R19") (pin "2") (pinfunction "2_2") (pintype "passive"))
    )
    (net (code "57") (name "Net-(IC2-L2)") (class "Default")
      (node (ref "IC2") (pin "8") (pinfunction "L2_8") (pintype "output"))
      (node (ref "R18") (pin "2") (pinfunction "2_2") (pintype "passive"))
    )
    (net (code "58") (name "Net-(IC2-L3)") (class "Default")
      (node (ref "IC2") (pin "9") (pinfunction "L3_9") (pintype "output"))
      (node (ref "R17") (pin "2") (pinfunction "2_2") (pintype "passive"))
    )
    (net (code "59") (name "Net-(IC2-L4)") (class "Default")
      (node (ref "IC2") (pin "10") (pinfunction "L4_10") (pintype "output"))
      (node (ref "R16") (pin "2") (pinfunction "2_2") (pintype "passive"))
    )
    (net (code "60") (name "Net-(IC2-L5)") (class "Default")
      (node (ref "IC2") (pin "11") (pinfunction "L5_11") (pintype "output"))
      (node (ref "R15") (pin "2") (pinfunction "2_2") (pintype "passive"))
    )
    (net (code "61") (name "Net-(IC2-L6)") (class "Default")
      (node (ref "IC2") (pin "12") (pinfunction "L6_12") (pintype "output"))
      (node (ref "R14") (pin "2") (pinfunction "2_2") (pintype "passive"))
    )
    (net (code "62") (name "Net-(IC2-L7)") (class "Default")
      (node (ref "IC2") (pin "13") (pinfunction "L7_13") (pintype "output"))
      (node (ref "R13") (pin "2") (pinfunction "2_2") (pintype "passive"))
    )
    (net (code "63") (name "Net-(IC2-L8)") (class "Default")
      (node (ref "IC2") (pin "15") (pinfunction "L8_15") (pintype "output"))
      (node (ref "R12") (pin "2") (pinfunction "2_2") (pintype "passive"))
    )
    (net (code "64") (name "Net-(IC2-L9)") (class "Default")
      (node (ref "IC2") (pin "16") (pinfunction "L9_16") (pintype "output"))
      (node (ref "R11") (pin "2") (pinfunction "2_2") (pintype "passive"))
    )
    (net (code "65") (name "Net-(IC2-L10)") (class "Default")
      (node (ref "IC2") (pin "17") (pinfunction "L10_17") (pintype "output"))
      (node (ref "R10") (pin "2") (pinfunction "2_2") (pintype "passive"))
    )
    (net (code "66") (name "Net-(IC2-L11)") (class "Default")
      (node (ref "IC2") (pin "18") (pinfunction "L11_18") (pintype "output"))
      (node (ref "R9") (pin "2") (pinfunction "2_2") (pintype "passive"))
    )
    (net (code "67") (name "Net-(IC2-L12)") (class "Default")
      (node (ref "IC2") (pin "19") (pinfunction "L12_19") (pintype "output"))
      (node (ref "R8") (pin "2") (pinfunction "2_2") (pintype "passive"))
    )
    (net (code "68") (name "Net-(IC2-L13)") (class "Default")
      (node (ref "IC2") (pin "20") (pinfunction "L13_20") (pintype "output"))
      (node (ref "R7") (pin "2") (pinfunction "2_2") (pintype "passive"))
    )
    (net (code "69") (name "Net-(IC2-L14)") (class "Default")
      (node (ref "IC2") (pin "21") (pinfunction "L14_21") (pintype "output"))
      (node (ref "R6") (pin "2") (pinfunction "2_2") (pintype "passive"))
    )
    (net (code "70") (name "Net-(IC2-L15)") (class "Default")
      (node (ref "IC2") (pin "22") (pinfunction "L15_22") (pintype "output"))
      (node (ref "R5") (pin "2") (pinfunction "2_2") (pintype "passive"))
    )
    (net (code "71") (name "Net-(IC3-L0)") (class "Default")
      (node (ref "IC3") (pin "6") (pinfunction "L0_6") (pintype "output"))
      (node (ref "R32") (pin "2") (pinfunction "2_2") (pintype "passive"))
    )
    (net (code "72") (name "Net-(IC3-L1)") (class "Default")
      (node (ref "IC3") (pin "7") (pinfunction "L1_7") (pintype "output"))
      (node (ref "R31") (pin "2") (pinfunction "2_2") (pintype "passive"))
    )
    (net (code "73") (name "Net-(IC3-L2)") (class "Default")
      (node (ref "IC3") (pin "8") (pinfunction "L2_8") (pintype "output"))
      (node (ref "R30") (pin "2") (pinfunction "2_2") (pintype "passive"))
    )
    (net (code "74") (name "Net-(IC3-L3)") (class "Default")
      (node (ref "IC3") (pin "9") (pinfunction "L3_9") (pintype "output"))
      (node (ref "R29") (pin "2") (pinfunction "2_2") (pintype "passive"))
    )
    (net (code "75") (name "Net-(IC3-L4)") (class "Default")
      (node (ref "IC3") (pin "10") (pinfunction "L4_10") (pintype "output"))
      (node (ref "R28") (pin "2") (pinfunction "2_2") (pintype "passive"))
    )
    (net (code "76") (name "Net-(IC3-L5)") (class "Default")
      (node (ref "IC3") (pin "11") (pinfunction "L5_11") (pintype "output"))
      (node (ref "R27") (pin "2") (pinfunction "2_2") (pintype "passive"))
    )
    (net (code "77") (name "Net-(IC3-L6)") (class "Default")
      (node (ref "IC3") (pin "12") (pinfunction "L6_12") (pintype "output"))
      (node (ref "R26") (pin "2") (pinfunction "2_2") (pintype "passive"))
    )
    (net (code "78") (name "Net-(IC3-L7)") (class "Default")
      (node (ref "IC3") (pin "13") (pinfunction "L7_13") (pintype "output"))
      (node (ref "R25") (pin "2") (pinfunction "2_2") (pintype "passive"))
    )
    (net (code "79") (name "Net-(IC3-L8)") (class "Default")
      (node (ref "IC3") (pin "15") (pinfunction "L8_15") (pintype "output"))
      (node (ref "R24") (pin "2") (pinfunction "2_2") (pintype "passive"))
    )
    (net (code "80") (name "Net-(IC3-L9)") (class "Default")
      (node (ref "IC3") (pin "16") (pinfunction "L9_16") (pintype "output"))
      (node (ref "R23") (pin "2") (pinfunction "2_2") (pintype "passive"))
    )
    (net (code "81") (name "Net-(IC3-L12)") (class "Default")
      (node (ref "IC3") (pin "19") (pinfunction "L12_19") (pintype "output"))
      (node (ref "R4") (pin "2") (pinfunction "2_2") (pintype "passive"))
    )
    (net (code "82") (name "Net-(IC3-L13)") (class "Default")
      (node (ref "IC3") (pin "20") (pinfunction "L13_20") (pintype "output"))
      (node (ref "R3") (pin "2") (pinfunction "2_2") (pintype "passive"))
    )
    (net (code "83") (name "Net-(IC3-L14)") (class "Default")
      (node (ref "IC3") (pin "21") (pinfunction "L14_21") (pintype "output"))
      (node (ref "R2") (pin "2") (pinfunction "2_2") (pintype "passive"))
    )
    (net (code "84") (name "Net-(IC3-L15)") (class "Default")
      (node (ref "IC3") (pin "22") (pinfunction "L15_22") (pintype "output"))
      (node (ref "R1") (pin "2") (pinfunction "2_2") (pintype "passive"))
    )
    (net (code "85") (name "SDI_MOSI") (class "Default")
      (node (ref "SERIAL") (pin "8") (pinfunction "8_8") (pintype "passive"))
    )
    (net (code "86") (name "SDI_SCLK") (class "Default")
      (node (ref "SERIAL") (pin "7") (pinfunction "7_7") (pintype "passive"))
    )
    (net (code "87") (name "SLIDER_IN") (class "Default")
      (node (ref "C6") (pin "1") (pinfunction "1_1") (pintype "passive"))
      (node (ref "JP1") (pin "2") (pinfunction "2_2") (pintype "passive"))
      (node (ref "JP2") (pin "2") (pinfunction "2_2") (pintype "passive"))
      (node (ref "POT1") (pin "2A") (pinfunction "S_2A") (pintype "passive"))
      (node (ref "POT1ALT") (pin "2A") (pinfunction "S_2A") (pintype "passive"))
      (node (ref "SERIAL") (pin "5") (pinfunction "5_5") (pintype "passive"))
    )
    (net (code "88") (name "unconnected-(IC1-INTA-Pad20)") (class "Default")
      (node (ref "IC1") (pin "20") (pinfunction "INTA_20") (pintype "output"))
    )
    (net (code "89") (name "unconnected-(IC1-INTB-Pad19)") (class "Default")
      (node (ref "IC1") (pin "19") (pinfunction "INTB_19") (pintype "output"))
    )
    (net (code "90") (name "unconnected-(IC3-L10-Pad17)") (class "Default")
      (node (ref "IC3") (pin "17") (pinfunction "L10_17") (pintype "output"))
    )
    (net (code "91") (name "unconnected-(IC3-L11-Pad18)") (class "Default")
      (node (ref "IC3") (pin "18") (pinfunction "L11_18") (pintype "output"))
    )
  )
)
